# ldet.net
KiCad netlist of a schematic drawn in EAGLE
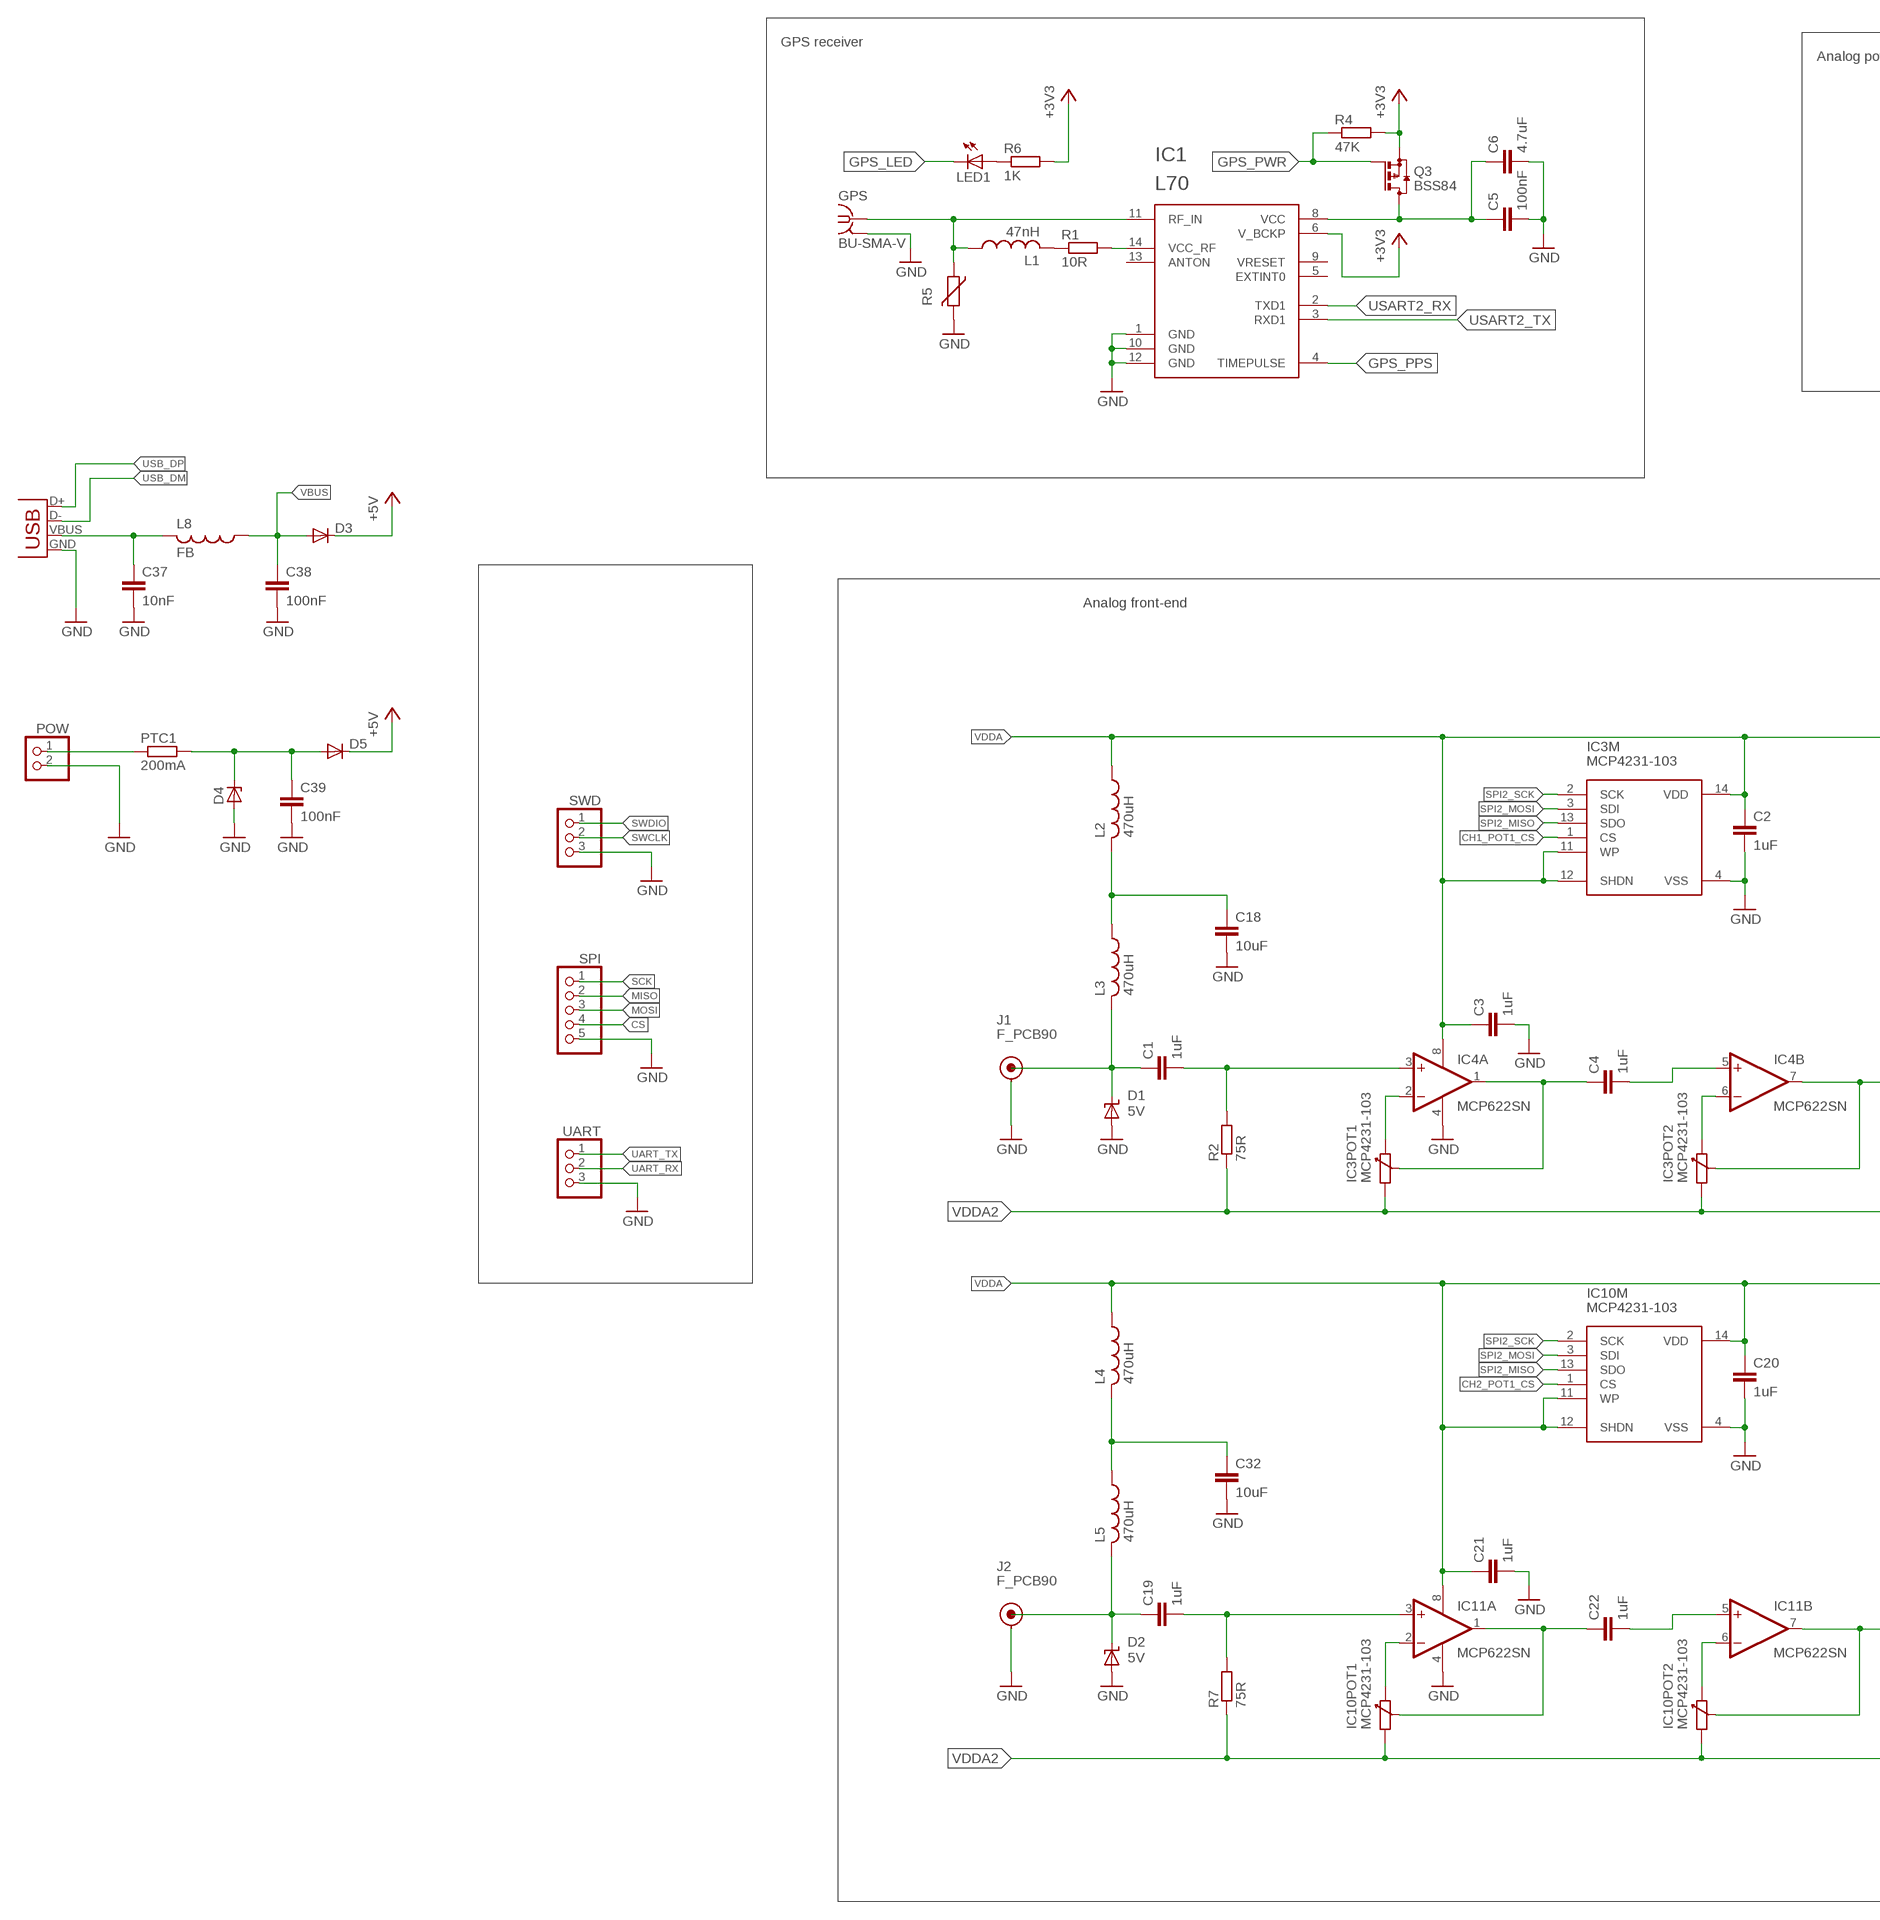
[diagram p0: schematic, sheet 1, part 1 of 2]
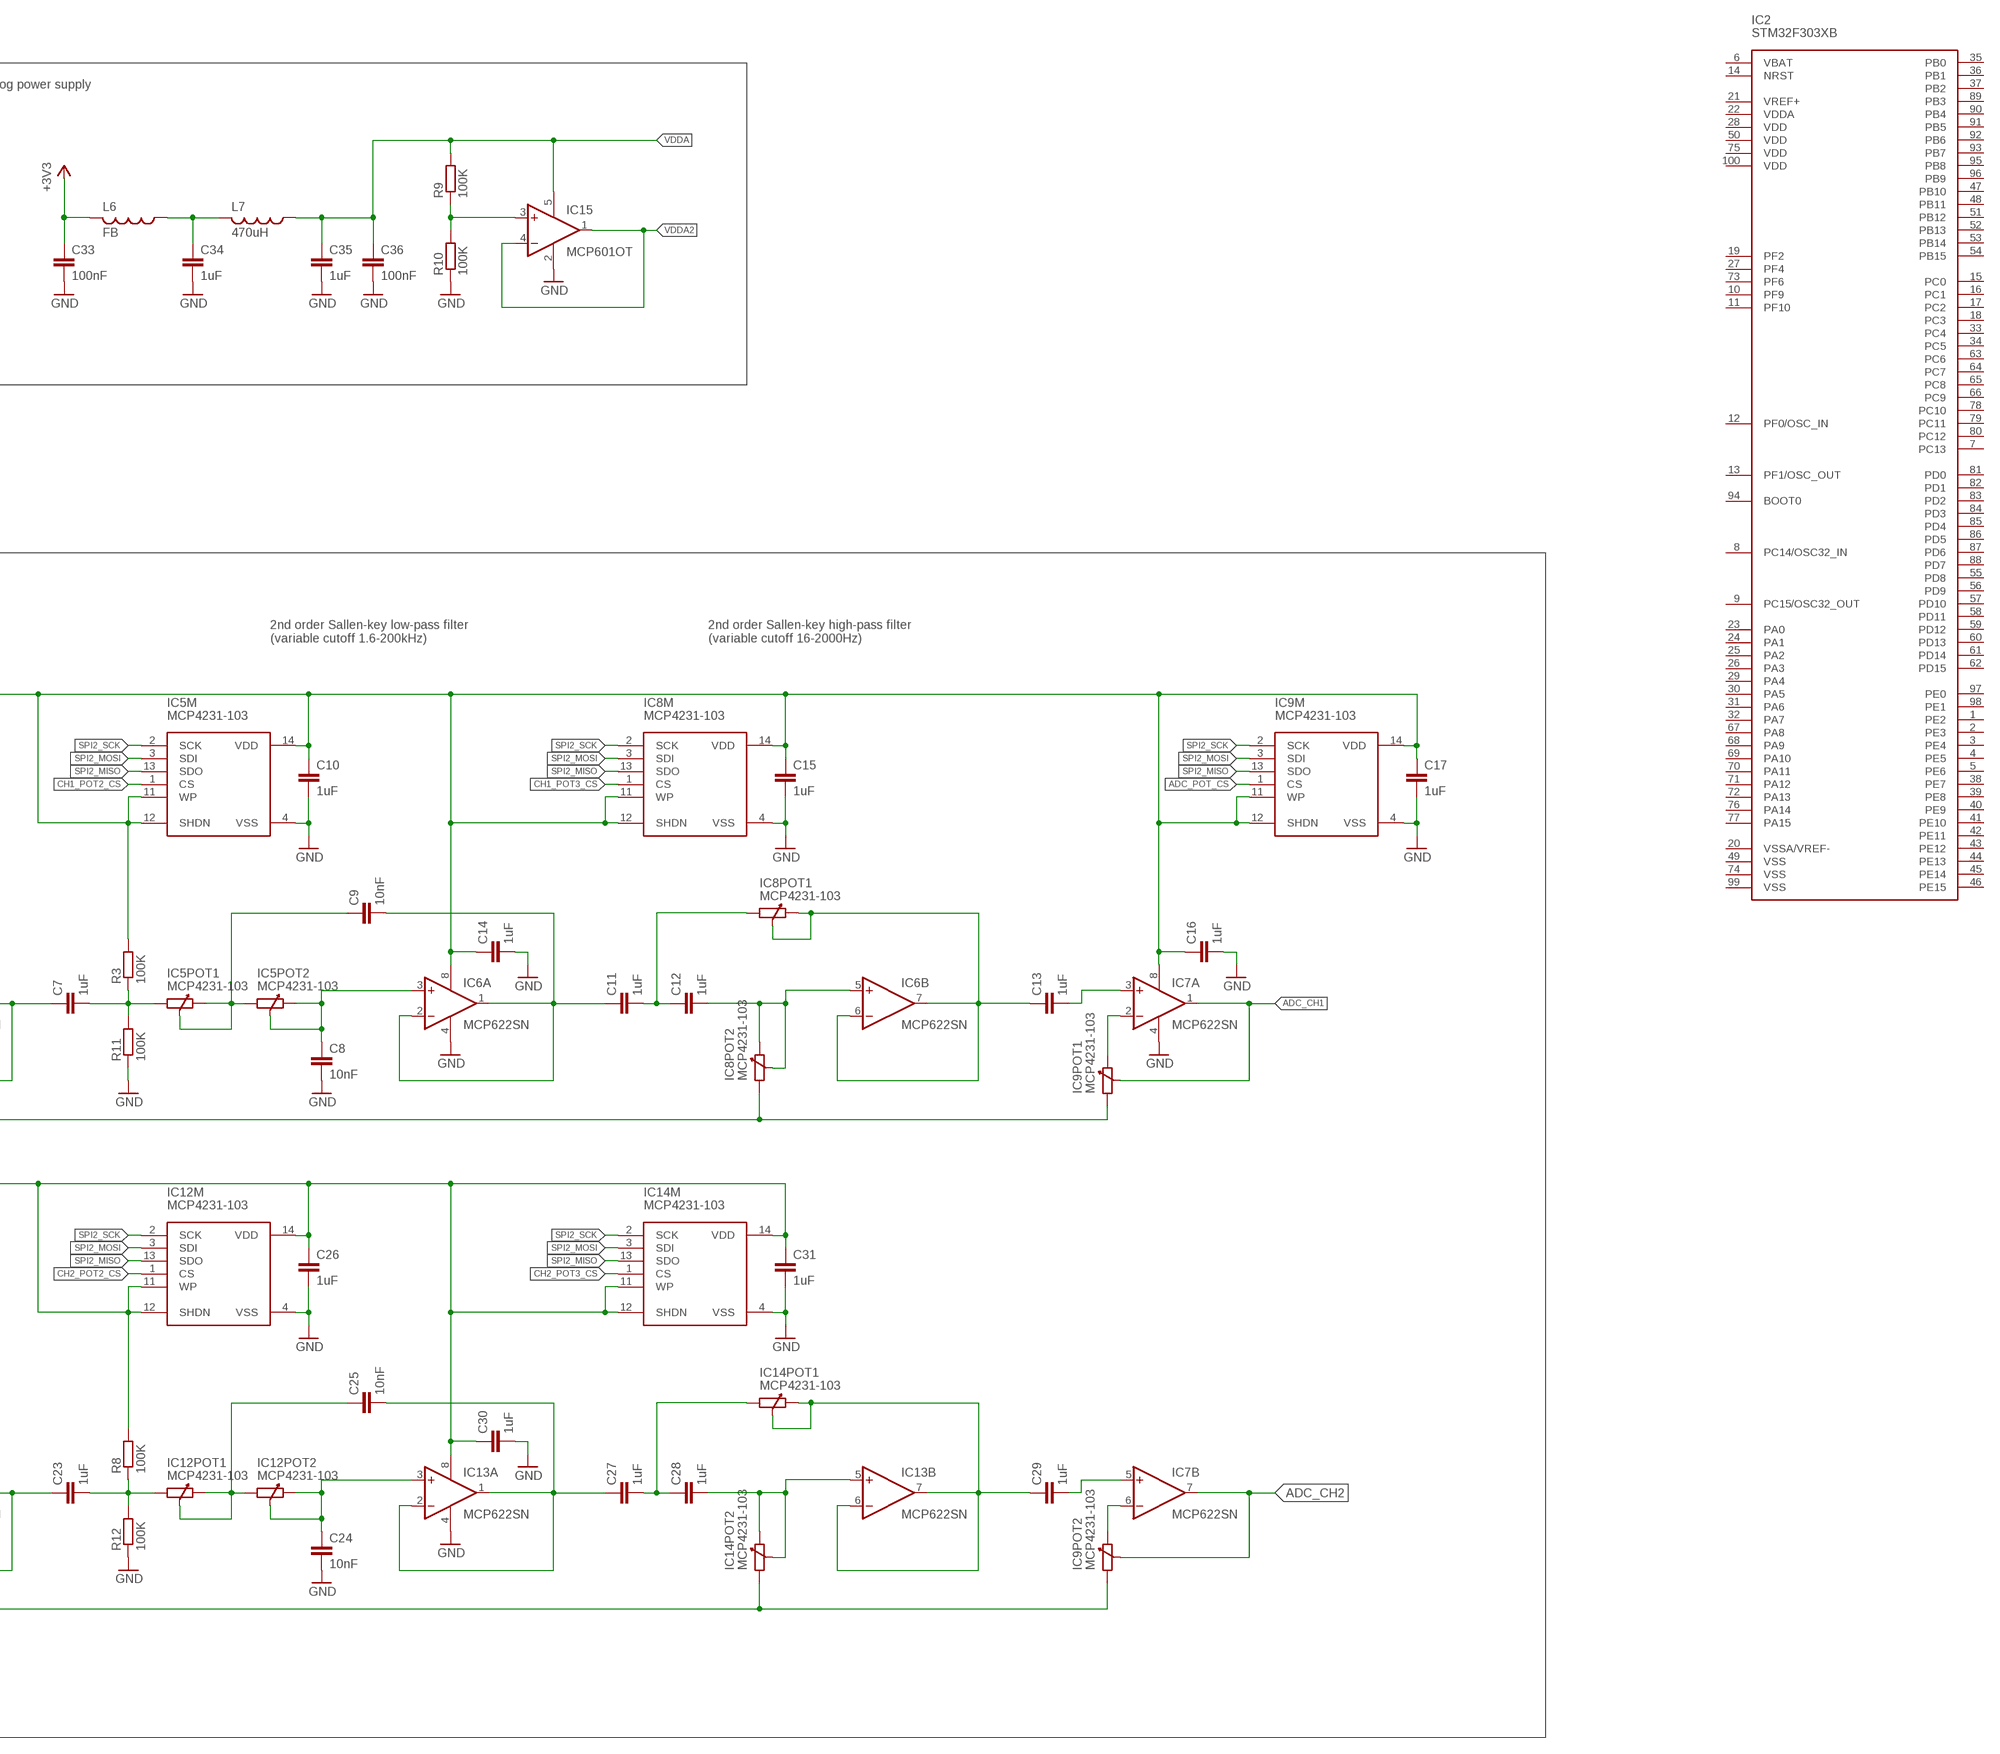
[diagram p1: schematic, sheet 1, part 2 of 2]

(export (version "E")
  (design (tool "Eeschema 10.0.6"))
  (components
    (comp (ref "C1")
      (value "1uF")
      (footprint "eagle-import:C0603")
      (libsource (lib "eagle-import") (part "C-EUC0603"))
    )
    (comp (ref "C2")
      (value "1uF")
      (footprint "eagle-import:C0603")
      (libsource (lib "eagle-import") (part "C-EUC0603"))
    )
    (comp (ref "C3")
      (value "1uF")
      (footprint "eagle-import:C0603")
      (libsource (lib "eagle-import") (part "C-EUC0603"))
    )
    (comp (ref "C4")
      (value "1uF")
      (footprint "eagle-import:C0603")
      (libsource (lib "eagle-import") (part "C-EUC0603"))
    )
    (comp (ref "C5")
      (value "100nF")
      (footprint "eagle-import:C0603")
      (libsource (lib "eagle-import") (part "C-EUC0603"))
    )
    (comp (ref "C6")
      (value "4.7uF")
      (footprint "eagle-import:C0805")
      (libsource (lib "eagle-import") (part "C-EUC0805"))
    )
    (comp (ref "C7")
      (value "1uF")
      (footprint "eagle-import:C0603")
      (libsource (lib "eagle-import") (part "C-EUC0603"))
    )
    (comp (ref "C8")
      (value "10nF")
      (footprint "eagle-import:C0603")
      (libsource (lib "eagle-import") (part "C-EUC0603"))
    )
    (comp (ref "C9")
      (value "10nF")
      (footprint "eagle-import:C0603")
      (libsource (lib "eagle-import") (part "C-EUC0603"))
    )
    (comp (ref "C10")
      (value "1uF")
      (footprint "eagle-import:C0603")
      (libsource (lib "eagle-import") (part "C-EUC0603"))
    )
    (comp (ref "C11")
      (value "1uF")
      (footprint "eagle-import:C0603")
      (libsource (lib "eagle-import") (part "C-EUC0603"))
    )
    (comp (ref "C12")
      (value "1uF")
      (footprint "eagle-import:C0603")
      (libsource (lib "eagle-import") (part "C-EUC0603"))
    )
    (comp (ref "C13")
      (value "1uF")
      (footprint "eagle-import:C0603")
      (libsource (lib "eagle-import") (part "C-EUC0603"))
    )
    (comp (ref "C14")
      (value "1uF")
      (footprint "eagle-import:C0603")
      (libsource (lib "eagle-import") (part "C-EUC0603"))
    )
    (comp (ref "C15")
      (value "1uF")
      (footprint "eagle-import:C0603")
      (libsource (lib "eagle-import") (part "C-EUC0603"))
    )
    (comp (ref "C16")
      (value "1uF")
      (footprint "eagle-import:C0603")
      (libsource (lib "eagle-import") (part "C-EUC0603"))
    )
    (comp (ref "C17")
      (value "1uF")
      (footprint "eagle-import:C0603")
      (libsource (lib "eagle-import") (part "C-EUC0603"))
    )
    (comp (ref "C18")
      (value "10uF")
      (footprint "eagle-import:C1206")
      (libsource (lib "eagle-import") (part "C-EUC1206"))
    )
    (comp (ref "C19")
      (value "1uF")
      (footprint "eagle-import:C0603")
      (libsource (lib "eagle-import") (part "C-EUC0603"))
    )
    (comp (ref "C20")
      (value "1uF")
      (footprint "eagle-import:C0603")
      (libsource (lib "eagle-import") (part "C-EUC0603"))
    )
    (comp (ref "C21")
      (value "1uF")
      (footprint "eagle-import:C0603")
      (libsource (lib "eagle-import") (part "C-EUC0603"))
    )
    (comp (ref "C22")
      (value "1uF")
      (footprint "eagle-import:C0603")
      (libsource (lib "eagle-import") (part "C-EUC0603"))
    )
    (comp (ref "C23")
      (value "1uF")
      (footprint "eagle-import:C0603")
      (libsource (lib "eagle-import") (part "C-EUC0603"))
    )
    (comp (ref "C24")
      (value "10nF")
      (footprint "eagle-import:C0603")
      (libsource (lib "eagle-import") (part "C-EUC0603"))
    )
    (comp (ref "C25")
      (value "10nF")
      (footprint "eagle-import:C0603")
      (libsource (lib "eagle-import") (part "C-EUC0603"))
    )
    (comp (ref "C26")
      (value "1uF")
      (footprint "eagle-import:C0603")
      (libsource (lib "eagle-import") (part "C-EUC0603"))
    )
    (comp (ref "C27")
      (value "1uF")
      (footprint "eagle-import:C0603")
      (libsource (lib "eagle-import") (part "C-EUC0603"))
    )
    (comp (ref "C28")
      (value "1uF")
      (footprint "eagle-import:C0603")
      (libsource (lib "eagle-import") (part "C-EUC0603"))
    )
    (comp (ref "C29")
      (value "1uF")
      (footprint "eagle-import:C0603")
      (libsource (lib "eagle-import") (part "C-EUC0603"))
    )
    (comp (ref "C30")
      (value "1uF")
      (footprint "eagle-import:C0603")
      (libsource (lib "eagle-import") (part "C-EUC0603"))
    )
    (comp (ref "C31")
      (value "1uF")
      (footprint "eagle-import:C0603")
      (libsource (lib "eagle-import") (part "C-EUC0603"))
    )
    (comp (ref "C32")
      (value "10uF")
      (footprint "eagle-import:C1206")
      (libsource (lib "eagle-import") (part "C-EUC1206"))
    )
    (comp (ref "C33")
      (value "100nF")
      (footprint "eagle-import:C0603")
      (libsource (lib "eagle-import") (part "C-EUC0603"))
    )
    (comp (ref "C34")
      (value "1uF")
      (footprint "eagle-import:C0603")
      (libsource (lib "eagle-import") (part "C-EUC0603"))
    )
    (comp (ref "C35")
      (value "1uF")
      (footprint "eagle-import:C0603")
      (libsource (lib "eagle-import") (part "C-EUC0603"))
    )
    (comp (ref "C36")
      (value "100nF")
      (footprint "eagle-import:C0603")
      (libsource (lib "eagle-import") (part "C-EUC0603"))
    )
    (comp (ref "C37")
      (value "10nF")
      (footprint "eagle-import:C0603")
      (libsource (lib "eagle-import") (part "C-EUC0603"))
    )
    (comp (ref "C38")
      (value "100nF")
      (footprint "eagle-import:C0603")
      (libsource (lib "eagle-import") (part "C-EUC0603"))
    )
    (comp (ref "C39")
      (value "100nF")
      (footprint "eagle-import:C0603")
      (libsource (lib "eagle-import") (part "C-EUC0603"))
    )
    (comp (ref "D1")
      (value "5V")
      (footprint "eagle-import:SMBJ")
      (libsource (lib "eagle-import") (part "SUPPRESSOR-SMBJ"))
    )
    (comp (ref "D2")
      (value "5V")
      (footprint "eagle-import:SMBJ")
      (libsource (lib "eagle-import") (part "SUPPRESSOR-SMBJ"))
    )
    (comp (ref "D3")
      (value "DIODE-SOD123")
      (footprint "eagle-import:SOD123")
      (libsource (lib "eagle-import") (part "DIODE-SOD123"))
    )
    (comp (ref "D4")
      (value "ZENER-DIODESMB")
      (footprint "eagle-import:SMB")
      (libsource (lib "eagle-import") (part "ZENER-DIODESMB"))
    )
    (comp (ref "D5")
      (value "DIODE-SOD123")
      (footprint "eagle-import:SOD123")
      (libsource (lib "eagle-import") (part "DIODE-SOD123"))
    )
    (comp (ref "GPS")
      (value "BU-SMA-V")
      (footprint "eagle-import:BU-SMA-V")
      (libsource (lib "eagle-import") (part "BU-SMA-V"))
    )
    (comp (ref "IC1")
      (value "L70")
      (footprint "eagle-import:L70")
      (libsource (lib "eagle-import") (part "L70"))
    )
    (comp (ref "IC2")
      (value "STM32F303XB")
      (footprint "eagle-import:TQFP100")
      (libsource (lib "eagle-import") (part "STM32F303XB"))
    )
    (comp (ref "IC3")
      (value "MCP4231-103")
      (footprint "eagle-import:SO14")
      (libsource (lib "eagle-import") (part "MCP4231"))
    )
    (comp (ref "IC4")
      (value "MCP622SN")
      (footprint "eagle-import:SO08")
      (libsource (lib "eagle-import") (part "MCP602SN"))
    )
    (comp (ref "IC5")
      (value "MCP4231-103")
      (footprint "eagle-import:SO14")
      (libsource (lib "eagle-import") (part "MCP4231"))
    )
    (comp (ref "IC6")
      (value "MCP622SN")
      (footprint "eagle-import:SO08")
      (libsource (lib "eagle-import") (part "MCP602SN"))
    )
    (comp (ref "IC7")
      (value "MCP622SN")
      (footprint "eagle-import:SO08")
      (libsource (lib "eagle-import") (part "MCP602SN"))
    )
    (comp (ref "IC8")
      (value "MCP4231-103")
      (footprint "eagle-import:SO14")
      (libsource (lib "eagle-import") (part "MCP4231"))
    )
    (comp (ref "IC9")
      (value "MCP4231-103")
      (footprint "eagle-import:SO14")
      (libsource (lib "eagle-import") (part "MCP4231"))
    )
    (comp (ref "IC10")
      (value "MCP4231-103")
      (footprint "eagle-import:SO14")
      (libsource (lib "eagle-import") (part "MCP4231"))
    )
    (comp (ref "IC11")
      (value "MCP622SN")
      (footprint "eagle-import:SO08")
      (libsource (lib "eagle-import") (part "MCP602SN"))
    )
    (comp (ref "IC12")
      (value "MCP4231-103")
      (footprint "eagle-import:SO14")
      (libsource (lib "eagle-import") (part "MCP4231"))
    )
    (comp (ref "IC13")
      (value "MCP622SN")
      (footprint "eagle-import:SO08")
      (libsource (lib "eagle-import") (part "MCP602SN"))
    )
    (comp (ref "IC14")
      (value "MCP4231-103")
      (footprint "eagle-import:SO14")
      (libsource (lib "eagle-import") (part "MCP4231"))
    )
    (comp (ref "IC15")
      (value "MCP601OT")
      (footprint "eagle-import:SOT23-5")
      (libsource (lib "eagle-import") (part "MCP601OT"))
    )
    (comp (ref "J1")
      (value "F_PCB90")
      (footprint "eagle-import:F_PCB_90")
      (libsource (lib "eagle-import") (part "F_PCB90"))
    )
    (comp (ref "J2")
      (value "F_PCB90")
      (footprint "eagle-import:F_PCB_90")
      (libsource (lib "eagle-import") (part "F_PCB90"))
    )
    (comp (ref "L1")
      (value "47nH")
      (footprint "eagle-import:L2012C")
      (libsource (lib "eagle-import") (part "L-USL2012C"))
    )
    (comp (ref "L2")
      (value "470uH")
      (footprint "eagle-import:L3225M")
      (fields (field (name "MPN") " LQH32CN471K23L"))
      (libsource (lib "eagle-import") (part "L-USL3225M"))
    )
    (comp (ref "L3")
      (value "470uH")
      (footprint "eagle-import:L3225M")
      (fields (field (name "MPN") "LQH32CN471K23L"))
      (libsource (lib "eagle-import") (part "L-USL3225M"))
    )
    (comp (ref "L4")
      (value "470uH")
      (footprint "eagle-import:L3225M")
      (fields (field (name "MPN") " LQH32CN471K23L"))
      (libsource (lib "eagle-import") (part "L-USL3225M"))
    )
    (comp (ref "L5")
      (value "470uH")
      (footprint "eagle-import:L3225M")
      (fields (field (name "MPN") "LQH32CN471K23L"))
      (libsource (lib "eagle-import") (part "L-USL3225M"))
    )
    (comp (ref "L6")
      (value "FB")
      (footprint "eagle-import:L2012C")
      (fields (field (name "MPN") " LQH32CN471K23L"))
      (libsource (lib "eagle-import") (part "L-USL2012C"))
    )
    (comp (ref "L7")
      (value "470uH")
      (footprint "eagle-import:L3225M")
      (fields (field (name "MPN") " LQH32CN471K23L"))
      (libsource (lib "eagle-import") (part "L-USL3225M"))
    )
    (comp (ref "L8")
      (value "FB")
      (footprint "eagle-import:L2012C")
      (fields (field (name "MPN") " LQH32CN471K23L"))
      (libsource (lib "eagle-import") (part "L-USL2012C"))
    )
    (comp (ref "LED1")
      (value "LEDCHIP-LED0603")
      (footprint "eagle-import:CHIP-LED0603")
      (libsource (lib "eagle-import") (part "LEDCHIP-LED0603"))
    )
    (comp (ref "POW")
      (value "PINHD-1X2")
      (footprint "eagle-import:1X02")
      (libsource (lib "eagle-import") (part "PINHD-1X2"))
    )
    (comp (ref "PTC1")
      (value "200mA")
      (footprint "eagle-import:R3225")
      (libsource (lib "eagle-import") (part "R-EU_R3225"))
    )
    (comp (ref "Q3")
      (value "BSS84")
      (footprint "eagle-import:SOT23")
      (libsource (lib "eagle-import") (part "BSS84"))
    )
    (comp (ref "R1")
      (value "10R")
      (footprint "eagle-import:R0603")
      (libsource (lib "eagle-import") (part "R-EU_R0603"))
    )
    (comp (ref "R2")
      (value "75R")
      (footprint "eagle-import:R0603")
      (libsource (lib "eagle-import") (part "R-EU_R0603"))
    )
    (comp (ref "R3")
      (value "100K")
      (footprint "eagle-import:R0603")
      (libsource (lib "eagle-import") (part "R-EU_R0603"))
    )
    (comp (ref "R4")
      (value "47K")
      (footprint "eagle-import:R0603")
      (libsource (lib "eagle-import") (part "R-EU_R0603"))
    )
    (comp (ref "R5")
      (value "VARISTORCN0805")
      (footprint "eagle-import:CT_CN0805")
      (libsource (lib "eagle-import") (part "VARISTORCN0805"))
    )
    (comp (ref "R6")
      (value "1K")
      (footprint "eagle-import:R0603")
      (libsource (lib "eagle-import") (part "R-EU_R0603"))
    )
    (comp (ref "R7")
      (value "75R")
      (footprint "eagle-import:R0603")
      (libsource (lib "eagle-import") (part "R-EU_R0603"))
    )
    (comp (ref "R8")
      (value "100K")
      (footprint "eagle-import:R0603")
      (libsource (lib "eagle-import") (part "R-EU_R0603"))
    )
    (comp (ref "R9")
      (value "100K")
      (footprint "eagle-import:R0603")
      (libsource (lib "eagle-import") (part "R-EU_R0603"))
    )
    (comp (ref "R10")
      (value "100K")
      (footprint "eagle-import:R0603")
      (libsource (lib "eagle-import") (part "R-EU_R0603"))
    )
    (comp (ref "R11")
      (value "100K")
      (footprint "eagle-import:R0603")
      (libsource (lib "eagle-import") (part "R-EU_R0603"))
    )
    (comp (ref "R12")
      (value "100K")
      (footprint "eagle-import:R0603")
      (libsource (lib "eagle-import") (part "R-EU_R0603"))
    )
    (comp (ref "SPI")
      (value "PINHD-1X5")
      (footprint "eagle-import:1X05")
      (libsource (lib "eagle-import") (part "PINHD-1X5"))
    )
    (comp (ref "SWD")
      (value "PINHD-1X3")
      (footprint "eagle-import:1X03")
      (libsource (lib "eagle-import") (part "PINHD-1X3"))
    )
    (comp (ref "UART")
      (value "PINHD-1X3")
      (footprint "eagle-import:1X03")
      (libsource (lib "eagle-import") (part "PINHD-1X3"))
    )
    (comp (ref "X1")
      (value "USBPTH")
      (footprint "eagle-import:USB-B-PTH")
      (libsource (lib "eagle-import") (part "USBPTH"))
    )
  )
  (nets
    (net (code "1") (name "+3V3") (class "Default")
      (node (ref "C33") (pin "1") (pinfunction "1_1") (pintype "passive"))
      (node (ref "IC1") (pin "6") (pinfunction "V_BCKP_6") (pintype "bidirectional"))
      (node (ref "L6") (pin "2") (pinfunction "2_2") (pintype "passive"))
      (node (ref "Q3") (pin "2") (pinfunction "S_2") (pintype "passive"))
      (node (ref "R4") (pin "2") (pinfunction "2_2") (pintype "passive"))
      (node (ref "R6") (pin "2") (pinfunction "2_2") (pintype "passive"))
    )
    (net (code "2") (name "+5V") (class "Default")
      (node (ref "D3") (pin "C") (pinfunction "C_C") (pintype "passive"))
      (node (ref "D5") (pin "C") (pinfunction "C_C") (pintype "passive"))
    )
    (net (code "3") (name "ADC_CH1") (class "Default")
      (node (ref "IC7") (pin "1") (pinfunction "OUT_1") (pintype "output"))
      (node (ref "IC9") (pin "6") (pinfunction "W_6") (pintype "bidirectional"))
    )
    (net (code "4") (name "ADC_CH2") (class "Default")
      (node (ref "IC7") (pin "7") (pinfunction "OUT_7") (pintype "output"))
      (node (ref "IC9") (pin "9") (pinfunction "W_9") (pintype "bidirectional"))
    )
    (net (code "5") (name "ADC_POT_CS") (class "Default")
      (node (ref "IC9") (pin "1") (pinfunction "CS_1") (pintype "bidirectional"))
    )
    (net (code "6") (name "CH1_POT1_CS") (class "Default")
      (node (ref "IC3") (pin "1") (pinfunction "CS_1") (pintype "bidirectional"))
    )
    (net (code "7") (name "CH1_POT2_CS") (class "Default")
      (node (ref "IC5") (pin "1") (pinfunction "CS_1") (pintype "bidirectional"))
    )
    (net (code "8") (name "CH1_POT3_CS") (class "Default")
      (node (ref "IC8") (pin "1") (pinfunction "CS_1") (pintype "bidirectional"))
    )
    (net (code "9") (name "CH2_POT1_CS") (class "Default")
      (node (ref "IC10") (pin "1") (pinfunction "CS_1") (pintype "bidirectional"))
    )
    (net (code "10") (name "CH2_POT2_CS") (class "Default")
      (node (ref "IC12") (pin "1") (pinfunction "CS_1") (pintype "bidirectional"))
    )
    (net (code "11") (name "CH2_POT3_CS") (class "Default")
      (node (ref "IC14") (pin "1") (pinfunction "CS_1") (pintype "bidirectional"))
    )
    (net (code "12") (name "CS") (class "Default")
      (node (ref "SPI") (pin "4") (pinfunction "4_4") (pintype "passive"))
    )
    (net (code "13") (name "GND") (class "Default")
      (node (ref "C10") (pin "2") (pinfunction "2_2") (pintype "passive"))
      (node (ref "C14") (pin "2") (pinfunction "2_2") (pintype "passive"))
      (node (ref "C15") (pin "2") (pinfunction "2_2") (pintype "passive"))
      (node (ref "C16") (pin "2") (pinfunction "2_2") (pintype "passive"))
      (node (ref "C17") (pin "2") (pinfunction "2_2") (pintype "passive"))
      (node (ref "C18") (pin "2") (pinfunction "2_2") (pintype "passive"))
      (node (ref "C2") (pin "2") (pinfunction "2_2") (pintype "passive"))
      (node (ref "C20") (pin "2") (pinfunction "2_2") (pintype "passive"))
      (node (ref "C21") (pin "2") (pinfunction "2_2") (pintype "passive"))
      (node (ref "C24") (pin "2") (pinfunction "2_2") (pintype "passive"))
      (node (ref "C26") (pin "2") (pinfunction "2_2") (pintype "passive"))
      (node (ref "C3") (pin "2") (pinfunction "2_2") (pintype "passive"))
      (node (ref "C30") (pin "2") (pinfunction "2_2") (pintype "passive"))
      (node (ref "C31") (pin "2") (pinfunction "2_2") (pintype "passive"))
      (node (ref "C32") (pin "2") (pinfunction "2_2") (pintype "passive"))
      (node (ref "C33") (pin "2") (pinfunction "2_2") (pintype "passive"))
      (node (ref "C34") (pin "2") (pinfunction "2_2") (pintype "passive"))
      (node (ref "C35") (pin "2") (pinfunction "2_2") (pintype "passive"))
      (node (ref "C36") (pin "2") (pinfunction "2_2") (pintype "passive"))
      (node (ref "C37") (pin "2") (pinfunction "2_2") (pintype "passive"))
      (node (ref "C38") (pin "2") (pinfunction "2_2") (pintype "passive"))
      (node (ref "C39") (pin "2") (pinfunction "2_2") (pintype "passive"))
      (node (ref "C5") (pin "2") (pinfunction "2_2") (pintype "passive"))
      (node (ref "C6") (pin "2") (pinfunction "2_2") (pintype "passive"))
      (node (ref "C8") (pin "2") (pinfunction "2_2") (pintype "passive"))
      (node (ref "D1") (pin "A") (pinfunction "A_A") (pintype "passive"))
      (node (ref "D2") (pin "A") (pinfunction "A_A") (pintype "passive"))
      (node (ref "D4") (pin "A") (pinfunction "A_A") (pintype "passive"))
      (node (ref "GPS") (pin "2") (pinfunction "2_2") (pintype "passive"))
      (node (ref "GPS") (pin "3") (pinfunction "2_3") (pintype "passive"))
      (node (ref "GPS") (pin "4") (pinfunction "2_4") (pintype "passive"))
      (node (ref "GPS") (pin "5") (pinfunction "2_5") (pintype "passive"))
      (node (ref "IC1") (pin "1") (pinfunction "GND_1") (pintype "bidirectional"))
      (node (ref "IC1") (pin "10") (pinfunction "GND_10") (pintype "bidirectional"))
      (node (ref "IC1") (pin "12") (pinfunction "GND_12") (pintype "bidirectional"))
      (node (ref "IC10") (pin "4") (pinfunction "VSS_4") (pintype "bidirectional"))
      (node (ref "IC11") (pin "4") (pinfunction "V-_4") (pintype "power_in"))
      (node (ref "IC12") (pin "4") (pinfunction "VSS_4") (pintype "bidirectional"))
      (node (ref "IC13") (pin "4") (pinfunction "V-_4") (pintype "power_in"))
      (node (ref "IC14") (pin "4") (pinfunction "VSS_4") (pintype "bidirectional"))
      (node (ref "IC15") (pin "2") (pinfunction "V-_2") (pintype "power_in"))
      (node (ref "IC3") (pin "4") (pinfunction "VSS_4") (pintype "bidirectional"))
      (node (ref "IC4") (pin "4") (pinfunction "V-_4") (pintype "power_in"))
      (node (ref "IC5") (pin "4") (pinfunction "VSS_4") (pintype "bidirectional"))
      (node (ref "IC6") (pin "4") (pinfunction "V-_4") (pintype "power_in"))
      (node (ref "IC7") (pin "4") (pinfunction "V-_4") (pintype "power_in"))
      (node (ref "IC8") (pin "4") (pinfunction "VSS_4") (pintype "bidirectional"))
      (node (ref "IC9") (pin "4") (pinfunction "VSS_4") (pintype "bidirectional"))
      (node (ref "J1") (pin "S1") (pinfunction "SHIELD_S1") (pintype "bidirectional"))
      (node (ref "J1") (pin "S2") (pinfunction "SHIELD_S2") (pintype "bidirectional"))
      (node (ref "J1") (pin "S3") (pinfunction "SHIELD_S3") (pintype "bidirectional"))
      (node (ref "J1") (pin "S4") (pinfunction "SHIELD_S4") (pintype "bidirectional"))
      (node (ref "J2") (pin "S1") (pinfunction "SHIELD_S1") (pintype "bidirectional"))
      (node (ref "J2") (pin "S2") (pinfunction "SHIELD_S2") (pintype "bidirectional"))
      (node (ref "J2") (pin "S3") (pinfunction "SHIELD_S3") (pintype "bidirectional"))
      (node (ref "J2") (pin "S4") (pinfunction "SHIELD_S4") (pintype "bidirectional"))
      (node (ref "POW") (pin "2") (pinfunction "2_2") (pintype "passive"))
      (node (ref "R10") (pin "1") (pinfunction "1_1") (pintype "passive"))
      (node (ref "R11") (pin "1") (pinfunction "1_1") (pintype "passive"))
      (node (ref "R12") (pin "1") (pinfunction "1_1") (pintype "passive"))
      (node (ref "R5") (pin "2") (pinfunction "2_2") (pintype "passive"))
      (node (ref "SPI") (pin "5") (pinfunction "5_5") (pintype "passive"))
      (node (ref "SWD") (pin "3") (pinfunction "3_3") (pintype "passive"))
      (node (ref "UART") (pin "3") (pinfunction "3_3") (pintype "passive"))
      (node (ref "X1") (pin "GND") (pinfunction "GND_GND") (pintype "bidirectional"))
    )
    (net (code "14") (name "GPS_LED") (class "Default")
      (node (ref "LED1") (pin "C") (pinfunction "C_C") (pintype "passive"))
    )
    (net (code "15") (name "GPS_PPS") (class "Default")
      (node (ref "IC1") (pin "4") (pinfunction "TIMEPULSE_4") (pintype "bidirectional"))
    )
    (net (code "16") (name "GPS_PWR") (class "Default")
      (node (ref "Q3") (pin "1") (pinfunction "G_1") (pintype "passive"))
      (node (ref "R4") (pin "1") (pinfunction "1_1") (pintype "passive"))
    )
    (net (code "17") (name "MISO") (class "Default")
      (node (ref "SPI") (pin "2") (pinfunction "2_2") (pintype "passive"))
    )
    (net (code "18") (name "MOSI") (class "Default")
      (node (ref "SPI") (pin "3") (pinfunction "3_3") (pintype "passive"))
    )
    (net (code "19") (name "Net-(C18-Pad1)") (class "Default")
      (node (ref "C18") (pin "1") (pinfunction "1_1") (pintype "passive"))
      (node (ref "L2") (pin "2") (pinfunction "2_2") (pintype "passive"))
      (node (ref "L3") (pin "1") (pinfunction "1_1") (pintype "passive"))
    )
    (net (code "20") (name "Net-(C32-Pad1)") (class "Default")
      (node (ref "C32") (pin "1") (pinfunction "1_1") (pintype "passive"))
      (node (ref "L4") (pin "2") (pinfunction "2_2") (pintype "passive"))
      (node (ref "L5") (pin "1") (pinfunction "1_1") (pintype "passive"))
    )
    (net (code "21") (name "Net-(C34-Pad1)") (class "Default")
      (node (ref "C34") (pin "1") (pinfunction "1_1") (pintype "passive"))
      (node (ref "L6") (pin "1") (pinfunction "1_1") (pintype "passive"))
      (node (ref "L7") (pin "2") (pinfunction "2_2") (pintype "passive"))
    )
    (net (code "22") (name "Net-(C37-Pad1)") (class "Default")
      (node (ref "C37") (pin "1") (pinfunction "1_1") (pintype "passive"))
      (node (ref "L8") (pin "2") (pinfunction "2_2") (pintype "passive"))
      (node (ref "X1") (pin "VBUS") (pinfunction "VBUS_VBUS") (pintype "bidirectional"))
    )
    (net (code "23") (name "Net-(C39-Pad1)") (class "Default")
      (node (ref "C39") (pin "1") (pinfunction "1_1") (pintype "passive"))
      (node (ref "D4") (pin "C") (pinfunction "C_C") (pintype "passive"))
      (node (ref "D5") (pin "A") (pinfunction "A_A") (pintype "passive"))
      (node (ref "PTC1") (pin "2") (pinfunction "2_2") (pintype "passive"))
    )
    (net (code "24") (name "Net-(IC1-RF_IN)") (class "Default")
      (node (ref "GPS") (pin "1") (pinfunction "1_1") (pintype "passive"))
      (node (ref "IC1") (pin "11") (pinfunction "RF_IN_11") (pintype "bidirectional"))
      (node (ref "L1") (pin "1") (pinfunction "1_1") (pintype "passive"))
      (node (ref "R5") (pin "1") (pinfunction "1_1") (pintype "passive"))
    )
    (net (code "25") (name "Net-(IC1-VCC)") (class "Default")
      (node (ref "C5") (pin "1") (pinfunction "1_1") (pintype "passive"))
      (node (ref "C6") (pin "1") (pinfunction "1_1") (pintype "passive"))
      (node (ref "IC1") (pin "8") (pinfunction "VCC_8") (pintype "bidirectional"))
      (node (ref "Q3") (pin "3") (pinfunction "D_3") (pintype "passive"))
    )
    (net (code "26") (name "Net-(IC1-VCC_RF)") (class "Default")
      (node (ref "IC1") (pin "14") (pinfunction "VCC_RF_14") (pintype "bidirectional"))
      (node (ref "R1") (pin "2") (pinfunction "2_2") (pintype "passive"))
    )
    (net (code "27") (name "Net-(IC3B-B)") (class "Default")
      (node (ref "IC3") (pin "5") (pinfunction "B_5") (pintype "bidirectional"))
      (node (ref "IC4") (pin "2") (pinfunction "-IN_2") (pintype "input"))
    )
    (net (code "28") (name "Net-(IC3B-W)") (class "Default")
      (node (ref "C4") (pin "1") (pinfunction "1_1") (pintype "passive"))
      (node (ref "IC3") (pin "6") (pinfunction "W_6") (pintype "bidirectional"))
      (node (ref "IC4") (pin "1") (pinfunction "OUT_1") (pintype "output"))
    )
    (net (code "29") (name "Net-(IC3C-B)") (class "Default")
      (node (ref "IC3") (pin "10") (pinfunction "B_10") (pintype "bidirectional"))
      (node (ref "IC4") (pin "6") (pinfunction "-IN_6") (pintype "input"))
    )
    (net (code "30") (name "Net-(IC3C-W)") (class "Default")
      (node (ref "C7") (pin "1") (pinfunction "1_1") (pintype "passive"))
      (node (ref "IC3") (pin "9") (pinfunction "W_9") (pintype "bidirectional"))
      (node (ref "IC4") (pin "7") (pinfunction "OUT_7") (pintype "output"))
    )
    (net (code "31") (name "Net-(IC4A-+IN)") (class "Default")
      (node (ref "C1") (pin "2") (pinfunction "2_2") (pintype "passive"))
      (node (ref "IC4") (pin "3") (pinfunction "+IN_3") (pintype "input"))
      (node (ref "R2") (pin "2") (pinfunction "2_2") (pintype "passive"))
    )
    (net (code "32") (name "Net-(IC4B-+IN)") (class "Default")
      (node (ref "C4") (pin "2") (pinfunction "2_2") (pintype "passive"))
      (node (ref "IC4") (pin "5") (pinfunction "+IN_5") (pintype "input"))
    )
    (net (code "33") (name "Net-(IC5B-A)") (class "Default")
      (node (ref "C7") (pin "2") (pinfunction "2_2") (pintype "passive"))
      (node (ref "IC5") (pin "7") (pinfunction "A_7") (pintype "bidirectional"))
      (node (ref "R11") (pin "2") (pinfunction "2_2") (pintype "passive"))
      (node (ref "R3") (pin "1") (pinfunction "1_1") (pintype "passive"))
    )
    (net (code "34") (name "Net-(IC5B-B)") (class "Default")
      (node (ref "C9") (pin "1") (pinfunction "1_1") (pintype "passive"))
      (node (ref "IC5") (pin "5") (pinfunction "B_5") (pintype "bidirectional"))
      (node (ref "IC5") (pin "6") (pinfunction "W_6") (pintype "bidirectional"))
      (node (ref "IC5") (pin "8") (pinfunction "A_8") (pintype "bidirectional"))
    )
    (net (code "35") (name "Net-(IC5C-B)") (class "Default")
      (node (ref "C8") (pin "1") (pinfunction "1_1") (pintype "passive"))
      (node (ref "IC5") (pin "10") (pinfunction "B_10") (pintype "bidirectional"))
      (node (ref "IC5") (pin "9") (pinfunction "W_9") (pintype "bidirectional"))
      (node (ref "IC6") (pin "3") (pinfunction "+IN_3") (pintype "input"))
    )
    (net (code "36") (name "Net-(IC6A--IN)") (class "Default")
      (node (ref "C11") (pin "1") (pinfunction "1_1") (pintype "passive"))
      (node (ref "C9") (pin "2") (pinfunction "2_2") (pintype "passive"))
      (node (ref "IC6") (pin "1") (pinfunction "OUT_1") (pintype "output"))
      (node (ref "IC6") (pin "2") (pinfunction "-IN_2") (pintype "input"))
    )
    (net (code "37") (name "Net-(IC6B-+IN)") (class "Default")
      (node (ref "C12") (pin "2") (pinfunction "2_2") (pintype "passive"))
      (node (ref "IC6") (pin "5") (pinfunction "+IN_5") (pintype "input"))
      (node (ref "IC8") (pin "10") (pinfunction "B_10") (pintype "bidirectional"))
      (node (ref "IC8") (pin "9") (pinfunction "W_9") (pintype "bidirectional"))
    )
    (net (code "38") (name "Net-(IC6B--IN)") (class "Default")
      (node (ref "C13") (pin "1") (pinfunction "1_1") (pintype "passive"))
      (node (ref "IC6") (pin "6") (pinfunction "-IN_6") (pintype "input"))
      (node (ref "IC6") (pin "7") (pinfunction "OUT_7") (pintype "output"))
      (node (ref "IC8") (pin "5") (pinfunction "B_5") (pintype "bidirectional"))
      (node (ref "IC8") (pin "6") (pinfunction "W_6") (pintype "bidirectional"))
    )
    (net (code "39") (name "Net-(IC7A-+IN)") (class "Default")
      (node (ref "C13") (pin "2") (pinfunction "2_2") (pintype "passive"))
      (node (ref "IC7") (pin "3") (pinfunction "+IN_3") (pintype "input"))
    )
    (net (code "40") (name "Net-(IC7A--IN)") (class "Default")
      (node (ref "IC7") (pin "2") (pinfunction "-IN_2") (pintype "input"))
      (node (ref "IC9") (pin "5") (pinfunction "B_5") (pintype "bidirectional"))
    )
    (net (code "41") (name "Net-(IC7B-+IN)") (class "Default")
      (node (ref "C29") (pin "2") (pinfunction "2_2") (pintype "passive"))
      (node (ref "IC7") (pin "5") (pinfunction "+IN_5") (pintype "input"))
    )
    (net (code "42") (name "Net-(IC7B--IN)") (class "Default")
      (node (ref "IC7") (pin "6") (pinfunction "-IN_6") (pintype "input"))
      (node (ref "IC9") (pin "10") (pinfunction "B_10") (pintype "bidirectional"))
    )
    (net (code "43") (name "Net-(IC8B-A)") (class "Default")
      (node (ref "C11") (pin "2") (pinfunction "2_2") (pintype "passive"))
      (node (ref "C12") (pin "1") (pinfunction "1_1") (pintype "passive"))
      (node (ref "IC8") (pin "7") (pinfunction "A_7") (pintype "bidirectional"))
    )
    (net (code "44") (name "Net-(IC10B-B)") (class "Default")
      (node (ref "IC10") (pin "5") (pinfunction "B_5") (pintype "bidirectional"))
      (node (ref "IC11") (pin "2") (pinfunction "-IN_2") (pintype "input"))
    )
    (net (code "45") (name "Net-(IC10B-W)") (class "Default")
      (node (ref "C22") (pin "1") (pinfunction "1_1") (pintype "passive"))
      (node (ref "IC10") (pin "6") (pinfunction "W_6") (pintype "bidirectional"))
      (node (ref "IC11") (pin "1") (pinfunction "OUT_1") (pintype "output"))
    )
    (net (code "46") (name "Net-(IC10C-B)") (class "Default")
      (node (ref "IC10") (pin "10") (pinfunction "B_10") (pintype "bidirectional"))
      (node (ref "IC11") (pin "6") (pinfunction "-IN_6") (pintype "input"))
    )
    (net (code "47") (name "Net-(IC10C-W)") (class "Default")
      (node (ref "C23") (pin "1") (pinfunction "1_1") (pintype "passive"))
      (node (ref "IC10") (pin "9") (pinfunction "W_9") (pintype "bidirectional"))
      (node (ref "IC11") (pin "7") (pinfunction "OUT_7") (pintype "output"))
    )
    (net (code "48") (name "Net-(IC11A-+IN)") (class "Default")
      (node (ref "C19") (pin "2") (pinfunction "2_2") (pintype "passive"))
      (node (ref "IC11") (pin "3") (pinfunction "+IN_3") (pintype "input"))
      (node (ref "R7") (pin "2") (pinfunction "2_2") (pintype "passive"))
    )
    (net (code "49") (name "Net-(IC11B-+IN)") (class "Default")
      (node (ref "C22") (pin "2") (pinfunction "2_2") (pintype "passive"))
      (node (ref "IC11") (pin "5") (pinfunction "+IN_5") (pintype "input"))
    )
    (net (code "50") (name "Net-(IC12B-A)") (class "Default")
      (node (ref "C23") (pin "2") (pinfunction "2_2") (pintype "passive"))
      (node (ref "IC12") (pin "7") (pinfunction "A_7") (pintype "bidirectional"))
      (node (ref "R12") (pin "2") (pinfunction "2_2") (pintype "passive"))
      (node (ref "R8") (pin "1") (pinfunction "1_1") (pintype "passive"))
    )
    (net (code "51") (name "Net-(IC12B-B)") (class "Default")
      (node (ref "C25") (pin "1") (pinfunction "1_1") (pintype "passive"))
      (node (ref "IC12") (pin "5") (pinfunction "B_5") (pintype "bidirectional"))
      (node (ref "IC12") (pin "6") (pinfunction "W_6") (pintype "bidirectional"))
      (node (ref "IC12") (pin "8") (pinfunction "A_8") (pintype "bidirectional"))
    )
    (net (code "52") (name "Net-(IC12C-B)") (class "Default")
      (node (ref "C24") (pin "1") (pinfunction "1_1") (pintype "passive"))
      (node (ref "IC12") (pin "10") (pinfunction "B_10") (pintype "bidirectional"))
      (node (ref "IC12") (pin "9") (pinfunction "W_9") (pintype "bidirectional"))
      (node (ref "IC13") (pin "3") (pinfunction "+IN_3") (pintype "input"))
    )
    (net (code "53") (name "Net-(IC13A--IN)") (class "Default")
      (node (ref "C25") (pin "2") (pinfunction "2_2") (pintype "passive"))
      (node (ref "C27") (pin "1") (pinfunction "1_1") (pintype "passive"))
      (node (ref "IC13") (pin "1") (pinfunction "OUT_1") (pintype "output"))
      (node (ref "IC13") (pin "2") (pinfunction "-IN_2") (pintype "input"))
    )
    (net (code "54") (name "Net-(IC13B-+IN)") (class "Default")
      (node (ref "C28") (pin "2") (pinfunction "2_2") (pintype "passive"))
      (node (ref "IC13") (pin "5") (pinfunction "+IN_5") (pintype "input"))
      (node (ref "IC14") (pin "10") (pinfunction "B_10") (pintype "bidirectional"))
      (node (ref "IC14") (pin "9") (pinfunction "W_9") (pintype "bidirectional"))
    )
    (net (code "55") (name "Net-(IC13B--IN)") (class "Default")
      (node (ref "C29") (pin "1") (pinfunction "1_1") (pintype "passive"))
      (node (ref "IC13") (pin "6") (pinfunction "-IN_6") (pintype "input"))
      (node (ref "IC13") (pin "7") (pinfunction "OUT_7") (pintype "output"))
      (node (ref "IC14") (pin "5") (pinfunction "B_5") (pintype "bidirectional"))
      (node (ref "IC14") (pin "6") (pinfunction "W_6") (pintype "bidirectional"))
    )
    (net (code "56") (name "Net-(IC14B-A)") (class "Default")
      (node (ref "C27") (pin "2") (pinfunction "2_2") (pintype "passive"))
      (node (ref "C28") (pin "1") (pinfunction "1_1") (pintype "passive"))
      (node (ref "IC14") (pin "7") (pinfunction "A_7") (pintype "bidirectional"))
    )
    (net (code "57") (name "Net-(IC15-+IN)") (class "Default")
      (node (ref "IC15") (pin "3") (pinfunction "+IN_3") (pintype "input"))
      (node (ref "R10") (pin "2") (pinfunction "2_2") (pintype "passive"))
      (node (ref "R9") (pin "1") (pinfunction "1_1") (pintype "passive"))
    )
    (net (code "58") (name "Net-(J1-CENTER)") (class "Default")
      (node (ref "C1") (pin "1") (pinfunction "1_1") (pintype "passive"))
      (node (ref "D1") (pin "C") (pinfunction "C_C") (pintype "passive"))
      (node (ref "J1") (pin "C") (pinfunction "CENTER_C") (pintype "bidirectional"))
      (node (ref "L3") (pin "2") (pinfunction "2_2") (pintype "passive"))
    )
    (net (code "59") (name "Net-(J2-CENTER)") (class "Default")
      (node (ref "C19") (pin "1") (pinfunction "1_1") (pintype "passive"))
      (node (ref "D2") (pin "C") (pinfunction "C_C") (pintype "passive"))
      (node (ref "J2") (pin "C") (pinfunction "CENTER_C") (pintype "bidirectional"))
      (node (ref "L5") (pin "2") (pinfunction "2_2") (pintype "passive"))
    )
    (net (code "60") (name "Net-(L1-Pad2)") (class "Default")
      (node (ref "L1") (pin "2") (pinfunction "2_2") (pintype "passive"))
      (node (ref "R1") (pin "1") (pinfunction "1_1") (pintype "passive"))
    )
    (net (code "61") (name "Net-(LED1-PadA)") (class "Default")
      (node (ref "LED1") (pin "A") (pinfunction "A_A") (pintype "passive"))
      (node (ref "R6") (pin "1") (pinfunction "1_1") (pintype "passive"))
    )
    (net (code "62") (name "Net-(POW-Pad1)") (class "Default")
      (node (ref "POW") (pin "1") (pinfunction "1_1") (pintype "passive"))
      (node (ref "PTC1") (pin "1") (pinfunction "1_1") (pintype "passive"))
    )
    (net (code "63") (name "SCK") (class "Default")
      (node (ref "SPI") (pin "1") (pinfunction "1_1") (pintype "passive"))
    )
    (net (code "64") (name "SPI2_MISO") (class "Default")
      (node (ref "IC10") (pin "13") (pinfunction "SDO_13") (pintype "bidirectional"))
      (node (ref "IC12") (pin "13") (pinfunction "SDO_13") (pintype "bidirectional"))
      (node (ref "IC14") (pin "13") (pinfunction "SDO_13") (pintype "bidirectional"))
      (node (ref "IC3") (pin "13") (pinfunction "SDO_13") (pintype "bidirectional"))
      (node (ref "IC5") (pin "13") (pinfunction "SDO_13") (pintype "bidirectional"))
      (node (ref "IC8") (pin "13") (pinfunction "SDO_13") (pintype "bidirectional"))
      (node (ref "IC9") (pin "13") (pinfunction "SDO_13") (pintype "bidirectional"))
    )
    (net (code "65") (name "SPI2_MOSI") (class "Default")
      (node (ref "IC10") (pin "3") (pinfunction "SDI_3") (pintype "bidirectional"))
      (node (ref "IC12") (pin "3") (pinfunction "SDI_3") (pintype "bidirectional"))
      (node (ref "IC14") (pin "3") (pinfunction "SDI_3") (pintype "bidirectional"))
      (node (ref "IC3") (pin "3") (pinfunction "SDI_3") (pintype "bidirectional"))
      (node (ref "IC5") (pin "3") (pinfunction "SDI_3") (pintype "bidirectional"))
      (node (ref "IC8") (pin "3") (pinfunction "SDI_3") (pintype "bidirectional"))
      (node (ref "IC9") (pin "3") (pinfunction "SDI_3") (pintype "bidirectional"))
    )
    (net (code "66") (name "SPI2_SCK") (class "Default")
      (node (ref "IC10") (pin "2") (pinfunction "SCK_2") (pintype "bidirectional"))
      (node (ref "IC12") (pin "2") (pinfunction "SCK_2") (pintype "bidirectional"))
      (node (ref "IC14") (pin "2") (pinfunction "SCK_2") (pintype "bidirectional"))
      (node (ref "IC3") (pin "2") (pinfunction "SCK_2") (pintype "bidirectional"))
      (node (ref "IC5") (pin "2") (pinfunction "SCK_2") (pintype "bidirectional"))
      (node (ref "IC8") (pin "2") (pinfunction "SCK_2") (pintype "bidirectional"))
      (node (ref "IC9") (pin "2") (pinfunction "SCK_2") (pintype "bidirectional"))
    )
    (net (code "67") (name "SWCLK") (class "Default")
      (node (ref "SWD") (pin "2") (pinfunction "2_2") (pintype "passive"))
    )
    (net (code "68") (name "SWDIO") (class "Default")
      (node (ref "SWD") (pin "1") (pinfunction "1_1") (pintype "passive"))
    )
    (net (code "69") (name "UART_RX") (class "Default")
      (node (ref "UART") (pin "2") (pinfunction "2_2") (pintype "passive"))
    )
    (net (code "70") (name "UART_TX") (class "Default")
      (node (ref "UART") (pin "1") (pinfunction "1_1") (pintype "passive"))
    )
    (net (code "71") (name "USART2_RX") (class "Default")
      (node (ref "IC1") (pin "2") (pinfunction "TXD1_2") (pintype "bidirectional"))
    )
    (net (code "72") (name "USART2_TX") (class "Default")
      (node (ref "IC1") (pin "3") (pinfunction "RXD1_3") (pintype "bidirectional"))
    )
    (net (code "73") (name "USB_DM") (class "Default")
      (node (ref "X1") (pin "D-") (pinfunction "D-_D-") (pintype "bidirectional"))
    )
    (net (code "74") (name "USB_DP") (class "Default")
      (node (ref "X1") (pin "D+") (pinfunction "D+_D+") (pintype "bidirectional"))
    )
    (net (code "75") (name "VBUS") (class "Default")
      (node (ref "C38") (pin "1") (pinfunction "1_1") (pintype "passive"))
      (node (ref "D3") (pin "A") (pinfunction "A_A") (pintype "passive"))
      (node (ref "L8") (pin "1") (pinfunction "1_1") (pintype "passive"))
    )
    (net (code "76") (name "VDDA") (class "Default")
      (node (ref "C10") (pin "1") (pinfunction "1_1") (pintype "passive"))
      (node (ref "C14") (pin "1") (pinfunction "1_1") (pintype "passive"))
      (node (ref "C15") (pin "1") (pinfunction "1_1") (pintype "passive"))
      (node (ref "C16") (pin "1") (pinfunction "1_1") (pintype "passive"))
      (node (ref "C17") (pin "1") (pinfunction "1_1") (pintype "passive"))
      (node (ref "C2") (pin "1") (pinfunction "1_1") (pintype "passive"))
      (node (ref "C20") (pin "1") (pinfunction "1_1") (pintype "passive"))
      (node (ref "C21") (pin "1") (pinfunction "1_1") (pintype "passive"))
      (node (ref "C26") (pin "1") (pinfunction "1_1") (pintype "passive"))
      (node (ref "C3") (pin "1") (pinfunction "1_1") (pintype "passive"))
      (node (ref "C30") (pin "1") (pinfunction "1_1") (pintype "passive"))
      (node (ref "C31") (pin "1") (pinfunction "1_1") (pintype "passive"))
      (node (ref "C35") (pin "1") (pinfunction "1_1") (pintype "passive"))
      (node (ref "C36") (pin "1") (pinfunction "1_1") (pintype "passive"))
      (node (ref "IC10") (pin "11") (pinfunction "WP_11") (pintype "bidirectional"))
      (node (ref "IC10") (pin "12") (pinfunction "SHDN_12") (pintype "bidirectional"))
      (node (ref "IC10") (pin "14") (pinfunction "VDD_14") (pintype "bidirectional"))
      (node (ref "IC11") (pin "8") (pinfunction "V+_8") (pintype "power_in"))
      (node (ref "IC12") (pin "11") (pinfunction "WP_11") (pintype "bidirectional"))
      (node (ref "IC12") (pin "12") (pinfunction "SHDN_12") (pintype "bidirectional"))
      (node (ref "IC12") (pin "14") (pinfunction "VDD_14") (pintype "bidirectional"))
      (node (ref "IC13") (pin "8") (pinfunction "V+_8") (pintype "power_in"))
      (node (ref "IC14") (pin "11") (pinfunction "WP_11") (pintype "bidirectional"))
      (node (ref "IC14") (pin "12") (pinfunction "SHDN_12") (pintype "bidirectional"))
      (node (ref "IC14") (pin "14") (pinfunction "VDD_14") (pintype "bidirectional"))
      (node (ref "IC15") (pin "5") (pinfunction "V+_5") (pintype "power_in"))
      (node (ref "IC3") (pin "11") (pinfunction "WP_11") (pintype "bidirectional"))
      (node (ref "IC3") (pin "12") (pinfunction "SHDN_12") (pintype "bidirectional"))
      (node (ref "IC3") (pin "14") (pinfunction "VDD_14") (pintype "bidirectional"))
      (node (ref "IC4") (pin "8") (pinfunction "V+_8") (pintype "power_in"))
      (node (ref "IC5") (pin "11") (pinfunction "WP_11") (pintype "bidirectional"))
      (node (ref "IC5") (pin "12") (pinfunction "SHDN_12") (pintype "bidirectional"))
      (node (ref "IC5") (pin "14") (pinfunction "VDD_14") (pintype "bidirectional"))
      (node (ref "IC6") (pin "8") (pinfunction "V+_8") (pintype "power_in"))
      (node (ref "IC7") (pin "8") (pinfunction "V+_8") (pintype "power_in"))
      (node (ref "IC8") (pin "11") (pinfunction "WP_11") (pintype "bidirectional"))
      (node (ref "IC8") (pin "12") (pinfunction "SHDN_12") (pintype "bidirectional"))
      (node (ref "IC8") (pin "14") (pinfunction "VDD_14") (pintype "bidirectional"))
      (node (ref "IC9") (pin "11") (pinfunction "WP_11") (pintype "bidirectional"))
      (node (ref "IC9") (pin "12") (pinfunction "SHDN_12") (pintype "bidirectional"))
      (node (ref "IC9") (pin "14") (pinfunction "VDD_14") (pintype "bidirectional"))
      (node (ref "L2") (pin "1") (pinfunction "1_1") (pintype "passive"))
      (node (ref "L4") (pin "1") (pinfunction "1_1") (pintype "passive"))
      (node (ref "L7") (pin "1") (pinfunction "1_1") (pintype "passive"))
      (node (ref "R3") (pin "2") (pinfunction "2_2") (pintype "passive"))
      (node (ref "R8") (pin "2") (pinfunction "2_2") (pintype "passive"))
      (node (ref "R9") (pin "2") (pinfunction "2_2") (pintype "passive"))
    )
    (net (code "77") (name "VDDA2") (class "Default")
      (node (ref "IC10") (pin "7") (pinfunction "A_7") (pintype "bidirectional"))
      (node (ref "IC10") (pin "8") (pinfunction "A_8") (pintype "bidirectional"))
      (node (ref "IC14") (pin "8") (pinfunction "A_8") (pintype "bidirectional"))
      (node (ref "IC15") (pin "1") (pinfunction "OUT_1") (pintype "output"))
      (node (ref "IC15") (pin "4") (pinfunction "-IN_4") (pintype "input"))
      (node (ref "IC3") (pin "7") (pinfunction "A_7") (pintype "bidirectional"))
      (node (ref "IC3") (pin "8") (pinfunction "A_8") (pintype "bidirectional"))
      (node (ref "IC8") (pin "8") (pinfunction "A_8") (pintype "bidirectional"))
      (node (ref "IC9") (pin "7") (pinfunction "A_7") (pintype "bidirectional"))
      (node (ref "IC9") (pin "8") (pinfunction "A_8") (pintype "bidirectional"))
      (node (ref "R2") (pin "1") (pinfunction "1_1") (pintype "passive"))
      (node (ref "R7") (pin "1") (pinfunction "1_1") (pintype "passive"))
    )
    (net (code "78") (name "unconnected-(IC1-ANTON-Pad13)") (class "Default")
      (node (ref "IC1") (pin "13") (pinfunction "ANTON_13") (pintype "bidirectional"))
    )
    (net (code "79") (name "unconnected-(IC1-EXTINT0-Pad5)") (class "Default")
      (node (ref "IC1") (pin "5") (pinfunction "EXTINT0_5") (pintype "bidirectional"))
    )
    (net (code "80") (name "unconnected-(IC1-VRESET-Pad9)") (class "Default")
      (node (ref "IC1") (pin "9") (pinfunction "VRESET_9") (pintype "bidirectional"))
    )
    (net (code "81") (name "unconnected-(IC2-BOOT0-Pad94)") (class "Default")
      (node (ref "IC2") (pin "94") (pinfunction "BOOT0_94") (pintype "bidirectional"))
    )
    (net (code "82") (name "unconnected-(IC2-NRST-Pad14)") (class "Default")
      (node (ref "IC2") (pin "14") (pinfunction "NRST_14") (pintype "bidirectional"))
    )
    (net (code "83") (name "unconnected-(IC2-PA0-Pad23)") (class "Default")
      (node (ref "IC2") (pin "23") (pinfunction "PA0_23") (pintype "bidirectional"))
    )
    (net (code "84") (name "unconnected-(IC2-PA1-Pad24)") (class "Default")
      (node (ref "IC2") (pin "24") (pinfunction "PA1_24") (pintype "bidirectional"))
    )
    (net (code "85") (name "unconnected-(IC2-PA2-Pad25)") (class "Default")
      (node (ref "IC2") (pin "25") (pinfunction "PA2_25") (pintype "bidirectional"))
    )
    (net (code "86") (name "unconnected-(IC2-PA3-Pad26)") (class "Default")
      (node (ref "IC2") (pin "26") (pinfunction "PA3_26") (pintype "bidirectional"))
    )
    (net (code "87") (name "unconnected-(IC2-PA4-Pad29)") (class "Default")
      (node (ref "IC2") (pin "29") (pinfunction "PA4_29") (pintype "bidirectional"))
    )
    (net (code "88") (name "unconnected-(IC2-PA5-Pad30)") (class "Default")
      (node (ref "IC2") (pin "30") (pinfunction "PA5_30") (pintype "bidirectional"))
    )
    (net (code "89") (name "unconnected-(IC2-PA6-Pad31)") (class "Default")
      (node (ref "IC2") (pin "31") (pinfunction "PA6_31") (pintype "bidirectional"))
    )
    (net (code "90") (name "unconnected-(IC2-PA7-Pad32)") (class "Default")
      (node (ref "IC2") (pin "32") (pinfunction "PA7_32") (pintype "bidirectional"))
    )
    (net (code "91") (name "unconnected-(IC2-PA8-Pad67)") (class "Default")
      (node (ref "IC2") (pin "67") (pinfunction "PA8_67") (pintype "bidirectional"))
    )
    (net (code "92") (name "unconnected-(IC2-PA9-Pad68)") (class "Default")
      (node (ref "IC2") (pin "68") (pinfunction "PA9_68") (pintype "bidirectional"))
    )
    (net (code "93") (name "unconnected-(IC2-PA10-Pad69)") (class "Default")
      (node (ref "IC2") (pin "69") (pinfunction "PA10_69") (pintype "bidirectional"))
    )
    (net (code "94") (name "unconnected-(IC2-PA11-Pad70)") (class "Default")
      (node (ref "IC2") (pin "70") (pinfunction "PA11_70") (pintype "bidirectional"))
    )
    (net (code "95") (name "unconnected-(IC2-PA12-Pad71)") (class "Default")
      (node (ref "IC2") (pin "71") (pinfunction "PA12_71") (pintype "bidirectional"))
    )
    (net (code "96") (name "unconnected-(IC2-PA13-Pad72)") (class "Default")
      (node (ref "IC2") (pin "72") (pinfunction "PA13_72") (pintype "bidirectional"))
    )
    (net (code "97") (name "unconnected-(IC2-PA14-Pad76)") (class "Default")
      (node (ref "IC2") (pin "76") (pinfunction "PA14_76") (pintype "bidirectional"))
    )
    (net (code "98") (name "unconnected-(IC2-PA15-Pad77)") (class "Default")
      (node (ref "IC2") (pin "77") (pinfunction "PA15_77") (pintype "bidirectional"))
    )
    (net (code "99") (name "unconnected-(IC2-PB0-Pad35)") (class "Default")
      (node (ref "IC2") (pin "35") (pinfunction "PB0_35") (pintype "bidirectional"))
    )
    (net (code "100") (name "unconnected-(IC2-PB1-Pad36)") (class "Default")
      (node (ref "IC2") (pin "36") (pinfunction "PB1_36") (pintype "bidirectional"))
    )
    (net (code "101") (name "unconnected-(IC2-PB2-Pad37)") (class "Default")
      (node (ref "IC2") (pin "37") (pinfunction "PB2_37") (pintype "bidirectional"))
    )
    (net (code "102") (name "unconnected-(IC2-PB3-Pad89)") (class "Default")
      (node (ref "IC2") (pin "89") (pinfunction "PB3_89") (pintype "bidirectional"))
    )
    (net (code "103") (name "unconnected-(IC2-PB4-Pad90)") (class "Default")
      (node (ref "IC2") (pin "90") (pinfunction "PB4_90") (pintype "bidirectional"))
    )
    (net (code "104") (name "unconnected-(IC2-PB5-Pad91)") (class "Default")
      (node (ref "IC2") (pin "91") (pinfunction "PB5_91") (pintype "bidirectional"))
    )
    (net (code "105") (name "unconnected-(IC2-PB6-Pad92)") (class "Default")
      (node (ref "IC2") (pin "92") (pinfunction "PB6_92") (pintype "bidirectional"))
    )
    (net (code "106") (name "unconnected-(IC2-PB7-Pad93)") (class "Default")
      (node (ref "IC2") (pin "93") (pinfunction "PB7_93") (pintype "bidirectional"))
    )
    (net (code "107") (name "unconnected-(IC2-PB8-Pad95)") (class "Default")
      (node (ref "IC2") (pin "95") (pinfunction "PB8_95") (pintype "bidirectional"))
    )
    (net (code "108") (name "unconnected-(IC2-PB9-Pad96)") (class "Default")
      (node (ref "IC2") (pin "96") (pinfunction "PB9_96") (pintype "bidirectional"))
    )
    (net (code "109") (name "unconnected-(IC2-PB10-Pad47)") (class "Default")
      (node (ref "IC2") (pin "47") (pinfunction "PB10_47") (pintype "bidirectional"))
    )
    (net (code "110") (name "unconnected-(IC2-PB11-Pad48)") (class "Default")
      (node (ref "IC2") (pin "48") (pinfunction "PB11_48") (pintype "bidirectional"))
    )
    (net (code "111") (name "unconnected-(IC2-PB12-Pad51)") (class "Default")
      (node (ref "IC2") (pin "51") (pinfunction "PB12_51") (pintype "bidirectional"))
    )
    (net (code "112") (name "unconnected-(IC2-PB13-Pad52)") (class "Default")
      (node (ref "IC2") (pin "52") (pinfunction "PB13_52") (pintype "bidirectional"))
    )
    (net (code "113") (name "unconnected-(IC2-PB14-Pad53)") (class "Default")
      (node (ref "IC2") (pin "53") (pinfunction "PB14_53") (pintype "bidirectional"))
    )
    (net (code "114") (name "unconnected-(IC2-PB15-Pad54)") (class "Default")
      (node (ref "IC2") (pin "54") (pinfunction "PB15_54") (pintype "bidirectional"))
    )
    (net (code "115") (name "unconnected-(IC2-PC0-Pad15)") (class "Default")
      (node (ref "IC2") (pin "15") (pinfunction "PC0_15") (pintype "bidirectional"))
    )
    (net (code "116") (name "unconnected-(IC2-PC1-Pad16)") (class "Default")
      (node (ref "IC2") (pin "16") (pinfunction "PC1_16") (pintype "bidirectional"))
    )
    (net (code "117") (name "unconnected-(IC2-PC2-Pad17)") (class "Default")
      (node (ref "IC2") (pin "17") (pinfunction "PC2_17") (pintype "bidirectional"))
    )
    (net (code "118") (name "unconnected-(IC2-PC3-Pad18)") (class "Default")
      (node (ref "IC2") (pin "18") (pinfunction "PC3_18") (pintype "bidirectional"))
    )
    (net (code "119") (name "unconnected-(IC2-PC4-Pad33)") (class "Default")
      (node (ref "IC2") (pin "33") (pinfunction "PC4_33") (pintype "bidirectional"))
    )
    (net (code "120") (name "unconnected-(IC2-PC5-Pad34)") (class "Default")
      (node (ref "IC2") (pin "34") (pinfunction "PC5_34") (pintype "bidirectional"))
    )
    (net (code "121") (name "unconnected-(IC2-PC6-Pad63)") (class "Default")
      (node (ref "IC2") (pin "63") (pinfunction "PC6_63") (pintype "bidirectional"))
    )
    (net (code "122") (name "unconnected-(IC2-PC7-Pad64)") (class "Default")
      (node (ref "IC2") (pin "64") (pinfunction "PC7_64") (pintype "bidirectional"))
    )
    (net (code "123") (name "unconnected-(IC2-PC8-Pad65)") (class "Default")
      (node (ref "IC2") (pin "65") (pinfunction "PC8_65") (pintype "bidirectional"))
    )
    (net (code "124") (name "unconnected-(IC2-PC9-Pad66)") (class "Default")
      (node (ref "IC2") (pin "66") (pinfunction "PC9_66") (pintype "bidirectional"))
    )
    (net (code "125") (name "unconnected-(IC2-PC10-Pad78)") (class "Default")
      (node (ref "IC2") (pin "78") (pinfunction "PC10_78") (pintype "bidirectional"))
    )
    (net (code "126") (name "unconnected-(IC2-PC11-Pad79)") (class "Default")
      (node (ref "IC2") (pin "79") (pinfunction "PC11_79") (pintype "bidirectional"))
    )
    (net (code "127") (name "unconnected-(IC2-PC12-Pad80)") (class "Default")
      (node (ref "IC2") (pin "80") (pinfunction "PC12_80") (pintype "bidirectional"))
    )
    (net (code "128") (name "unconnected-(IC2-PC13-Pad7)") (class "Default")
      (node (ref "IC2") (pin "7") (pinfunction "PC13_7") (pintype "bidirectional"))
    )
    (net (code "129") (name "unconnected-(IC2-PC14{slash}OSC32_IN-Pad8)") (class "Default")
      (node (ref "IC2") (pin "8") (pinfunction "PC14/OSC32_IN_8") (pintype "bidirectional"))
    )
    (net (code "130") (name "unconnected-(IC2-PC15{slash}OSC32_OUT-Pad9)") (class "Default")
      (node (ref "IC2") (pin "9") (pinfunction "PC15/OSC32_OUT_9") (pintype "bidirectional"))
    )
    (net (code "131") (name "unconnected-(IC2-PD0-Pad81)") (class "Default")
      (node (ref "IC2") (pin "81") (pinfunction "PD0_81") (pintype "bidirectional"))
    )
    (net (code "132") (name "unconnected-(IC2-PD1-Pad82)") (class "Default")
      (node (ref "IC2") (pin "82") (pinfunction "PD1_82") (pintype "bidirectional"))
    )
    (net (code "133") (name "unconnected-(IC2-PD2-Pad83)") (class "Default")
      (node (ref "IC2") (pin "83") (pinfunction "PD2_83") (pintype "bidirectional"))
    )
    (net (code "134") (name "unconnected-(IC2-PD3-Pad84)") (class "Default")
      (node (ref "IC2") (pin "84") (pinfunction "PD3_84") (pintype "bidirectional"))
    )
    (net (code "135") (name "unconnected-(IC2-PD4-Pad85)") (class "Default")
      (node (ref "IC2") (pin "85") (pinfunction "PD4_85") (pintype "bidirectional"))
    )
    (net (code "136") (name "unconnected-(IC2-PD5-Pad86)") (class "Default")
      (node (ref "IC2") (pin "86") (pinfunction "PD5_86") (pintype "bidirectional"))
    )
    (net (code "137") (name "unconnected-(IC2-PD6-Pad87)") (class "Default")
      (node (ref "IC2") (pin "87") (pinfunction "PD6_87") (pintype "bidirectional"))
    )
    (net (code "138") (name "unconnected-(IC2-PD7-Pad88)") (class "Default")
      (node (ref "IC2") (pin "88") (pinfunction "PD7_88") (pintype "bidirectional"))
    )
    (net (code "139") (name "unconnected-(IC2-PD8-Pad55)") (class "Default")
      (node (ref "IC2") (pin "55") (pinfunction "PD8_55") (pintype "bidirectional"))
    )
    (net (code "140") (name "unconnected-(IC2-PD9-Pad56)") (class "Default")
      (node (ref "IC2") (pin "56") (pinfunction "PD9_56") (pintype "bidirectional"))
    )
    (net (code "141") (name "unconnected-(IC2-PD10-Pad57)") (class "Default")
      (node (ref "IC2") (pin "57") (pinfunction "PD10_57") (pintype "bidirectional"))
    )
    (net (code "142") (name "unconnected-(IC2-PD11-Pad58)") (class "Default")
      (node (ref "IC2") (pin "58") (pinfunction "PD11_58") (pintype "bidirectional"))
    )
    (net (code "143") (name "unconnected-(IC2-PD12-Pad59)") (class "Default")
      (node (ref "IC2") (pin "59") (pinfunction "PD12_59") (pintype "bidirectional"))
    )
    (net (code "144") (name "unconnected-(IC2-PD13-Pad60)") (class "Default")
      (node (ref "IC2") (pin "60") (pinfunction "PD13_60") (pintype "bidirectional"))
    )
    (net (code "145") (name "unconnected-(IC2-PD14-Pad61)") (class "Default")
      (node (ref "IC2") (pin "61") (pinfunction "PD14_61") (pintype "bidirectional"))
    )
    (net (code "146") (name "unconnected-(IC2-PD15-Pad62)") (class "Default")
      (node (ref "IC2") (pin "62") (pinfunction "PD15_62") (pintype "bidirectional"))
    )
    (net (code "147") (name "unconnected-(IC2-PE0-Pad97)") (class "Default")
      (node (ref "IC2") (pin "97") (pinfunction "PE0_97") (pintype "bidirectional"))
    )
    (net (code "148") (name "unconnected-(IC2-PE1-Pad98)") (class "Default")
      (node (ref "IC2") (pin "98") (pinfunction "PE1_98") (pintype "bidirectional"))
    )
    (net (code "149") (name "unconnected-(IC2-PE2-Pad1)") (class "Default")
      (node (ref "IC2") (pin "1") (pinfunction "PE2_1") (pintype "bidirectional"))
    )
    (net (code "150") (name "unconnected-(IC2-PE3-Pad2)") (class "Default")
      (node (ref "IC2") (pin "2") (pinfunction "PE3_2") (pintype "bidirectional"))
    )
    (net (code "151") (name "unconnected-(IC2-PE4-Pad3)") (class "Default")
      (node (ref "IC2") (pin "3") (pinfunction "PE4_3") (pintype "bidirectional"))
    )
    (net (code "152") (name "unconnected-(IC2-PE5-Pad4)") (class "Default")
      (node (ref "IC2") (pin "4") (pinfunction "PE5_4") (pintype "bidirectional"))
    )
    (net (code "153") (name "unconnected-(IC2-PE6-Pad5)") (class "Default")
      (node (ref "IC2") (pin "5") (pinfunction "PE6_5") (pintype "bidirectional"))
    )
    (net (code "154") (name "unconnected-(IC2-PE7-Pad38)") (class "Default")
      (node (ref "IC2") (pin "38") (pinfunction "PE7_38") (pintype "bidirectional"))
    )
    (net (code "155") (name "unconnected-(IC2-PE8-Pad39)") (class "Default")
      (node (ref "IC2") (pin "39") (pinfunction "PE8_39") (pintype "bidirectional"))
    )
    (net (code "156") (name "unconnected-(IC2-PE9-Pad40)") (class "Default")
      (node (ref "IC2") (pin "40") (pinfunction "PE9_40") (pintype "bidirectional"))
    )
    (net (code "157") (name "unconnected-(IC2-PE10-Pad41)") (class "Default")
      (node (ref "IC2") (pin "41") (pinfunction "PE10_41") (pintype "bidirectional"))
    )
    (net (code "158") (name "unconnected-(IC2-PE11-Pad42)") (class "Default")
      (node (ref "IC2") (pin "42") (pinfunction "PE11_42") (pintype "bidirectional"))
    )
    (net (code "159") (name "unconnected-(IC2-PE12-Pad43)") (class "Default")
      (node (ref "IC2") (pin "43") (pinfunction "PE12_43") (pintype "bidirectional"))
    )
    (net (code "160") (name "unconnected-(IC2-PE13-Pad44)") (class "Default")
      (node (ref "IC2") (pin "44") (pinfunction "PE13_44") (pintype "bidirectional"))
    )
    (net (code "161") (name "unconnected-(IC2-PE14-Pad45)") (class "Default")
      (node (ref "IC2") (pin "45") (pinfunction "PE14_45") (pintype "bidirectional"))
    )
    (net (code "162") (name "unconnected-(IC2-PE15-Pad46)") (class "Default")
      (node (ref "IC2") (pin "46") (pinfunction "PE15_46") (pintype "bidirectional"))
    )
    (net (code "163") (name "unconnected-(IC2-PF0{slash}OSC_IN-Pad12)") (class "Default")
      (node (ref "IC2") (pin "12") (pinfunction "PF0/OSC_IN_12") (pintype "bidirectional"))
    )
    (net (code "164") (name "unconnected-(IC2-PF1{slash}OSC_OUT-Pad13)") (class "Default")
      (node (ref "IC2") (pin "13") (pinfunction "PF1/OSC_OUT_13") (pintype "bidirectional"))
    )
    (net (code "165") (name "unconnected-(IC2-PF2-Pad19)") (class "Default")
      (node (ref "IC2") (pin "19") (pinfunction "PF2_19") (pintype "bidirectional"))
    )
    (net (code "166") (name "unconnected-(IC2-PF4-Pad27)") (class "Default")
      (node (ref "IC2") (pin "27") (pinfunction "PF4_27") (pintype "bidirectional"))
    )
    (net (code "167") (name "unconnected-(IC2-PF6-Pad73)") (class "Default")
      (node (ref "IC2") (pin "73") (pinfunction "PF6_73") (pintype "bidirectional"))
    )
    (net (code "168") (name "unconnected-(IC2-PF9-Pad10)") (class "Default")
      (node (ref "IC2") (pin "10") (pinfunction "PF9_10") (pintype "bidirectional"))
    )
    (net (code "169") (name "unconnected-(IC2-PF10-Pad11)") (class "Default")
      (node (ref "IC2") (pin "11") (pinfunction "PF10_11") (pintype "bidirectional"))
    )
    (net (code "170") (name "unconnected-(IC2-VBAT-Pad6)") (class "Default")
      (node (ref "IC2") (pin "6") (pinfunction "VBAT_6") (pintype "bidirectional"))
    )
    (net (code "171") (name "unconnected-(IC2-VDD-Pad28)") (class "Default")
      (node (ref "IC2") (pin "28") (pinfunction "VDD_28") (pintype "bidirectional"))
    )
    (net (code "172") (name "unconnected-(IC2-VDD-Pad50)") (class "Default")
      (node (ref "IC2") (pin "50") (pinfunction "VDD_50") (pintype "bidirectional"))
    )
    (net (code "173") (name "unconnected-(IC2-VDD-Pad75)") (class "Default")
      (node (ref "IC2") (pin "75") (pinfunction "VDD_75") (pintype "bidirectional"))
    )
    (net (code "174") (name "unconnected-(IC2-VDD-Pad100)") (class "Default")
      (node (ref "IC2") (pin "100") (pinfunction "VDD_100") (pintype "bidirectional"))
    )
    (net (code "175") (name "unconnected-(IC2-VDDA-Pad22)") (class "Default")
      (node (ref "IC2") (pin "22") (pinfunction "VDDA_22") (pintype "bidirectional"))
    )
    (net (code "176") (name "unconnected-(IC2-VREF+-Pad21)") (class "Default")
      (node (ref "IC2") (pin "21") (pinfunction "VREF+_21") (pintype "bidirectional"))
    )
    (net (code "177") (name "unconnected-(IC2-VSS-Pad49)") (class "Default")
      (node (ref "IC2") (pin "49") (pinfunction "VSS_49") (pintype "bidirectional"))
    )
    (net (code "178") (name "unconnected-(IC2-VSS-Pad74)") (class "Default")
      (node (ref "IC2") (pin "74") (pinfunction "VSS_74") (pintype "bidirectional"))
    )
    (net (code "179") (name "unconnected-(IC2-VSS-Pad99)") (class "Default")
      (node (ref "IC2") (pin "99") (pinfunction "VSS_99") (pintype "bidirectional"))
    )
    (net (code "180") (name "unconnected-(IC2-VSSA{slash}VREF--Pad20)") (class "Default")
      (node (ref "IC2") (pin "20") (pinfunction "VSSA/VREF-_20") (pintype "bidirectional"))
    )
  )
)
